# DB25-relay-HV-control.net
KiCad netlist of a schematic drawn in Altium Designer
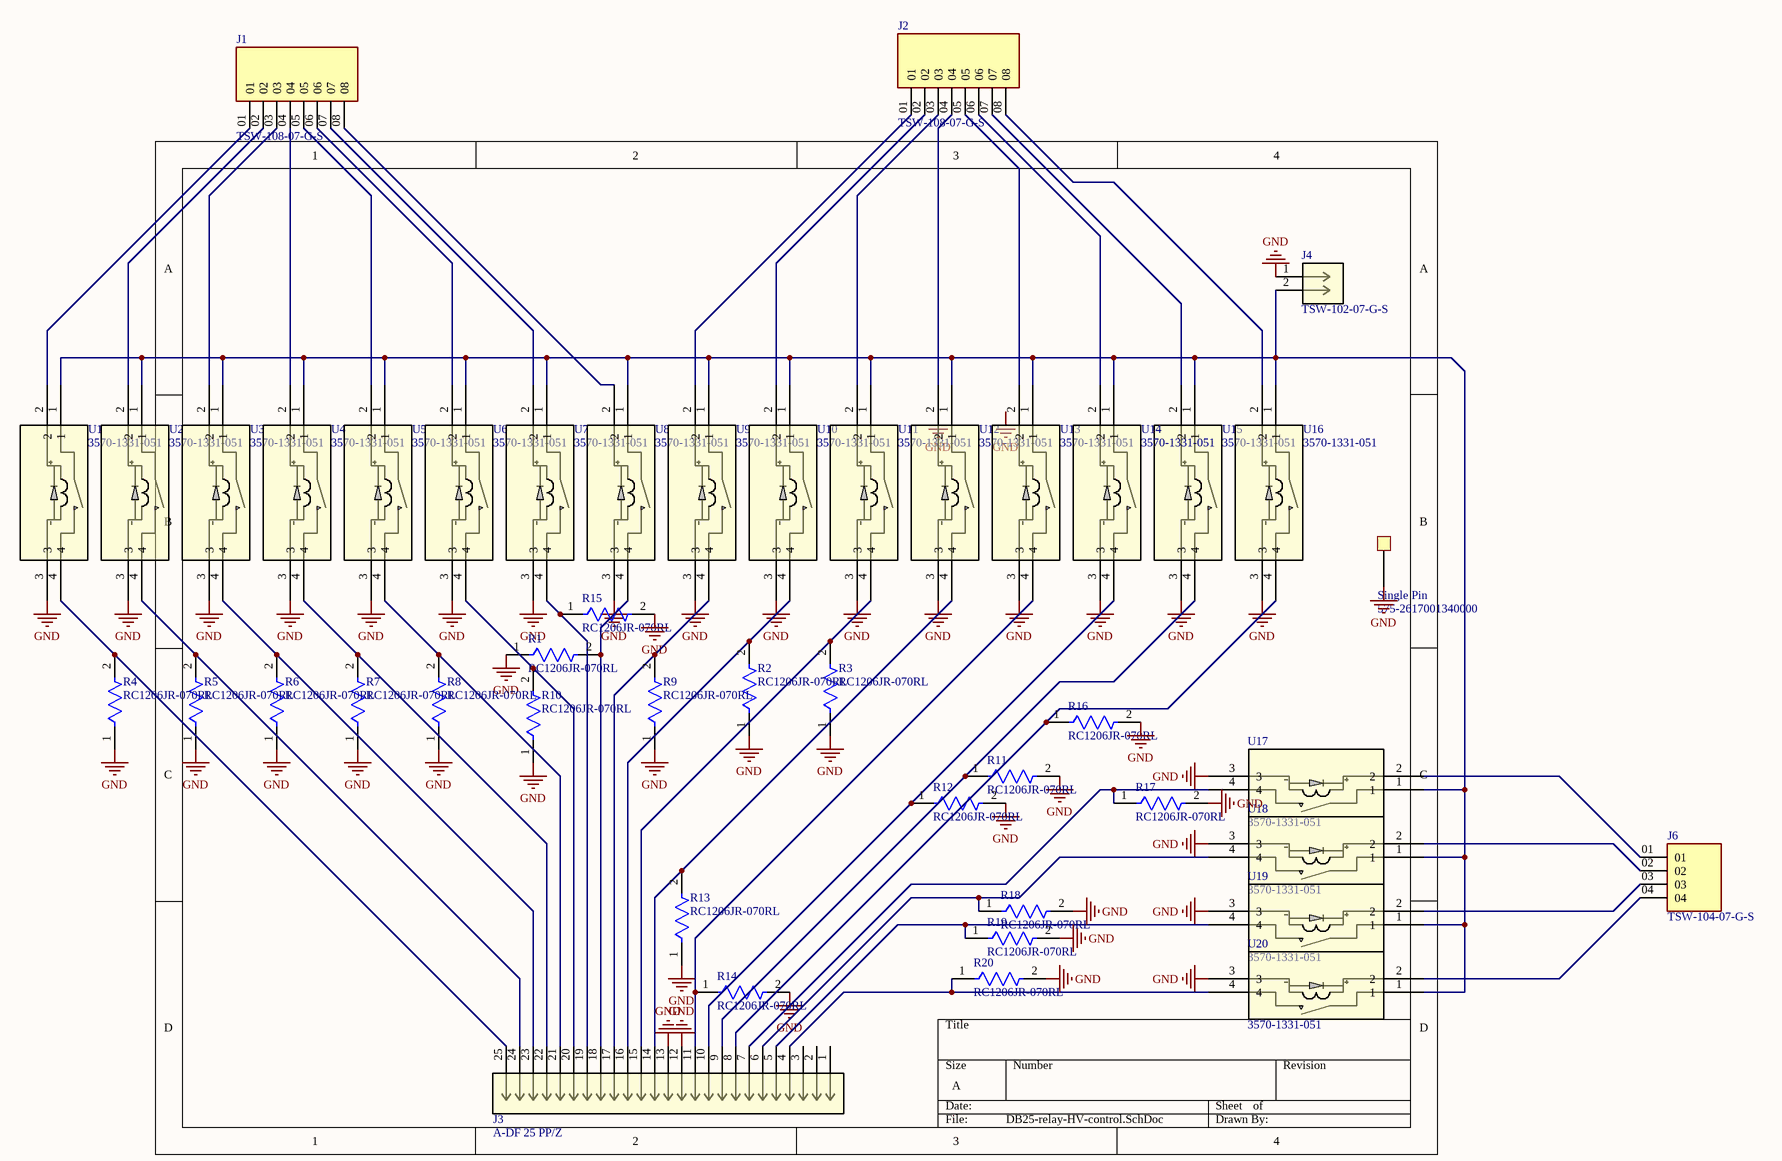
[diagram p0: DB25-relay-HV-control.SchDoc]

(export (version "E")
  (design (tool "Eeschema 10.0.6"))
  (components
    (comp (ref "J1")
      (value "TSW-108-07-G-S")
      (footprint "SAMTEC_TSW-108-07-G-S")
      (description "TSW - Samtec 2.54mm Pin Header 10.92mm Overall Pin Length (07) - Fast Stock")
      (fields (field (name "MF") "Samtec Inc."))
      (libsource (lib "SchlibLafe") (part "TSW-108-07-G-S"))
    )
    (comp (ref "J2")
      (value "TSW-108-07-G-S")
      (footprint "SAMTEC_TSW-108-07-G-S")
      (description "TSW - Samtec 2.54mm Pin Header 10.92mm Overall Pin Length (07) - Fast Stock")
      (fields (field (name "MF") "Samtec Inc."))
      (libsource (lib "SchlibLafe") (part "TSW-108-07-G-S"))
    )
    (comp (ref "J3")
      (value "A-DF 25 PP/Z")
      (footprint "CONN_A-DF 25 PPZ_ASM")
      (description "No Description Available")
      (fields (field (name "COPYRIGHT") "Copyright (C) 2024 Ultra Librarian. All rights reserved."))
      (libsource (lib "SchlibLafe") (part "A-DF 25 PPZ"))
    )
    (comp (ref "J4")
      (value "TSW-102-07-G-S")
      (footprint "CON2_1X2_TU_TSW")
      (description "No Description Available")
      (fields (field (name "COPYRIGHT") "Copyright (C) 2024 Ultra Librarian. All rights reserved."))
      (libsource (lib "SchlibLafe") (part "TSW-102-07-G-S"))
    )
    (comp (ref "J5")
      (value "Single Pin")
      (footprint "Single PC Pin")
      (fields (field (name "SUPPLIER PART NUMBER 1") "575-2617001340000"))
      (libsource (lib "SchlibLafe") (part "Single PC Pin"))
    )
    (comp (ref "J6")
      (value "TSW-104-07-G-S")
      (footprint "SAMTEC_TSW-104-07-G-S")
      (fields (field (name "MP") "altium_native_batch"))
      (libsource (lib "SchlibLafe") (part "TSW-104-07-G-S"))
    )
    (comp (ref "R1")
      (value "RC1206JR-070RL")
      (footprint "FP-RC1206-MFG")
      (description "RES SMD 0 OHM JUMPER 1/4W 1206")
      (fields
        (field (name "MANUFACTURER") "YAGEO")
        (field (name "OCTOPART") "https://octopart.com/rc1206jr-070rl-yageo-40025601")
      )
      (libsource (lib "Altium Content Vault") (part "1029c3af85768c4190bb7ad29bc67b5"))
    )
    (comp (ref "R2")
      (value "RC1206JR-070RL")
      (footprint "FP-RC1206-MFG")
      (description "RES SMD 0 OHM JUMPER 1/4W 1206")
      (fields
        (field (name "MANUFACTURER") "YAGEO")
        (field (name "OCTOPART") "https://octopart.com/rc1206jr-070rl-yageo-40025601")
      )
      (libsource (lib "Altium Content Vault") (part "1029c3af85768c4190bb7ad29bc67b5"))
    )
    (comp (ref "R3")
      (value "RC1206JR-070RL")
      (footprint "FP-RC1206-MFG")
      (description "RES SMD 0 OHM JUMPER 1/4W 1206")
      (fields
        (field (name "MANUFACTURER") "YAGEO")
        (field (name "OCTOPART") "https://octopart.com/rc1206jr-070rl-yageo-40025601")
      )
      (libsource (lib "Altium Content Vault") (part "1029c3af85768c4190bb7ad29bc67b5"))
    )
    (comp (ref "R4")
      (value "RC1206JR-070RL")
      (footprint "FP-RC1206-MFG")
      (description "RES SMD 0 OHM JUMPER 1/4W 1206")
      (fields
        (field (name "MANUFACTURER") "YAGEO")
        (field (name "OCTOPART") "https://octopart.com/rc1206jr-070rl-yageo-40025601")
      )
      (libsource (lib "Altium Content Vault") (part "1029c3af85768c4190bb7ad29bc67b5"))
    )
    (comp (ref "R5")
      (value "RC1206JR-070RL")
      (footprint "FP-RC1206-MFG")
      (description "RES SMD 0 OHM JUMPER 1/4W 1206")
      (fields
        (field (name "MANUFACTURER") "YAGEO")
        (field (name "OCTOPART") "https://octopart.com/rc1206jr-070rl-yageo-40025601")
      )
      (libsource (lib "Altium Content Vault") (part "1029c3af85768c4190bb7ad29bc67b5"))
    )
    (comp (ref "R6")
      (value "RC1206JR-070RL")
      (footprint "FP-RC1206-MFG")
      (description "RES SMD 0 OHM JUMPER 1/4W 1206")
      (fields
        (field (name "MANUFACTURER") "YAGEO")
        (field (name "OCTOPART") "https://octopart.com/rc1206jr-070rl-yageo-40025601")
      )
      (libsource (lib "Altium Content Vault") (part "1029c3af85768c4190bb7ad29bc67b5"))
    )
    (comp (ref "R7")
      (value "RC1206JR-070RL")
      (footprint "FP-RC1206-MFG")
      (description "RES SMD 0 OHM JUMPER 1/4W 1206")
      (fields
        (field (name "MANUFACTURER") "YAGEO")
        (field (name "OCTOPART") "https://octopart.com/rc1206jr-070rl-yageo-40025601")
      )
      (libsource (lib "Altium Content Vault") (part "1029c3af85768c4190bb7ad29bc67b5"))
    )
    (comp (ref "R8")
      (value "RC1206JR-070RL")
      (footprint "FP-RC1206-MFG")
      (description "RES SMD 0 OHM JUMPER 1/4W 1206")
      (fields
        (field (name "MANUFACTURER") "YAGEO")
        (field (name "OCTOPART") "https://octopart.com/rc1206jr-070rl-yageo-40025601")
      )
      (libsource (lib "Altium Content Vault") (part "1029c3af85768c4190bb7ad29bc67b5"))
    )
    (comp (ref "R9")
      (value "RC1206JR-070RL")
      (footprint "FP-RC1206-MFG")
      (description "RES SMD 0 OHM JUMPER 1/4W 1206")
      (fields
        (field (name "MANUFACTURER") "YAGEO")
        (field (name "OCTOPART") "https://octopart.com/rc1206jr-070rl-yageo-40025601")
      )
      (libsource (lib "Altium Content Vault") (part "1029c3af85768c4190bb7ad29bc67b5"))
    )
    (comp (ref "R10")
      (value "RC1206JR-070RL")
      (footprint "FP-RC1206-MFG")
      (description "RES SMD 0 OHM JUMPER 1/4W 1206")
      (fields
        (field (name "MANUFACTURER") "YAGEO")
        (field (name "OCTOPART") "https://octopart.com/rc1206jr-070rl-yageo-40025601")
      )
      (libsource (lib "Altium Content Vault") (part "1029c3af85768c4190bb7ad29bc67b5"))
    )
    (comp (ref "R11")
      (value "RC1206JR-070RL")
      (footprint "FP-RC1206-MFG")
      (description "RES SMD 0 OHM JUMPER 1/4W 1206")
      (fields
        (field (name "MANUFACTURER") "YAGEO")
        (field (name "OCTOPART") "https://octopart.com/rc1206jr-070rl-yageo-40025601")
      )
      (libsource (lib "Altium Content Vault") (part "1029c3af85768c4190bb7ad29bc67b5"))
    )
    (comp (ref "R12")
      (value "RC1206JR-070RL")
      (footprint "FP-RC1206-MFG")
      (description "RES SMD 0 OHM JUMPER 1/4W 1206")
      (fields
        (field (name "MANUFACTURER") "YAGEO")
        (field (name "OCTOPART") "https://octopart.com/rc1206jr-070rl-yageo-40025601")
      )
      (libsource (lib "Altium Content Vault") (part "1029c3af85768c4190bb7ad29bc67b5"))
    )
    (comp (ref "R13")
      (value "RC1206JR-070RL")
      (footprint "FP-RC1206-MFG")
      (description "RES SMD 0 OHM JUMPER 1/4W 1206")
      (fields
        (field (name "MANUFACTURER") "YAGEO")
        (field (name "OCTOPART") "https://octopart.com/rc1206jr-070rl-yageo-40025601")
      )
      (libsource (lib "Altium Content Vault") (part "1029c3af85768c4190bb7ad29bc67b5"))
    )
    (comp (ref "R14")
      (value "RC1206JR-070RL")
      (footprint "FP-RC1206-MFG")
      (description "RES SMD 0 OHM JUMPER 1/4W 1206")
      (fields
        (field (name "MANUFACTURER") "YAGEO")
        (field (name "OCTOPART") "https://octopart.com/rc1206jr-070rl-yageo-40025601")
      )
      (libsource (lib "Altium Content Vault") (part "1029c3af85768c4190bb7ad29bc67b5"))
    )
    (comp (ref "R15")
      (value "RC1206JR-070RL")
      (footprint "FP-RC1206-MFG")
      (description "RES SMD 0 OHM JUMPER 1/4W 1206")
      (fields
        (field (name "MANUFACTURER") "YAGEO")
        (field (name "OCTOPART") "https://octopart.com/rc1206jr-070rl-yageo-40025601")
      )
      (libsource (lib "Altium Content Vault") (part "1029c3af85768c4190bb7ad29bc67b5"))
    )
    (comp (ref "R16")
      (value "RC1206JR-070RL")
      (footprint "FP-RC1206-MFG")
      (description "RES SMD 0 OHM JUMPER 1/4W 1206")
      (fields
        (field (name "MANUFACTURER") "YAGEO")
        (field (name "OCTOPART") "https://octopart.com/rc1206jr-070rl-yageo-40025601")
      )
      (libsource (lib "Altium Content Vault") (part "1029c3af85768c4190bb7ad29bc67b5"))
    )
    (comp (ref "R17")
      (value "RC1206JR-070RL")
      (footprint "FP-RC1206-MFG")
      (description "RES SMD 0 OHM JUMPER 1/4W 1206")
      (fields
        (field (name "MANUFACTURER") "YAGEO")
        (field (name "OCTOPART") "https://octopart.com/rc1206jr-070rl-yageo-40025601")
      )
      (libsource (lib "Altium Content Vault") (part "1029c3af85768c4190bb7ad29bc67b5"))
    )
    (comp (ref "R18")
      (value "RC1206JR-070RL")
      (footprint "FP-RC1206-MFG")
      (description "RES SMD 0 OHM JUMPER 1/4W 1206")
      (fields
        (field (name "MANUFACTURER") "YAGEO")
        (field (name "OCTOPART") "https://octopart.com/rc1206jr-070rl-yageo-40025601")
      )
      (libsource (lib "Altium Content Vault") (part "1029c3af85768c4190bb7ad29bc67b5"))
    )
    (comp (ref "R19")
      (value "RC1206JR-070RL")
      (footprint "FP-RC1206-MFG")
      (description "RES SMD 0 OHM JUMPER 1/4W 1206")
      (fields
        (field (name "MANUFACTURER") "YAGEO")
        (field (name "OCTOPART") "https://octopart.com/rc1206jr-070rl-yageo-40025601")
      )
      (libsource (lib "Altium Content Vault") (part "1029c3af85768c4190bb7ad29bc67b5"))
    )
    (comp (ref "R20")
      (value "RC1206JR-070RL")
      (footprint "FP-RC1206-MFG")
      (description "RES SMD 0 OHM JUMPER 1/4W 1206")
      (fields
        (field (name "MANUFACTURER") "YAGEO")
        (field (name "OCTOPART") "https://octopart.com/rc1206jr-070rl-yageo-40025601")
      )
      (libsource (lib "Altium Content Vault") (part "1029c3af85768c4190bb7ad29bc67b5"))
    )
    (comp (ref "U1")
      (value "3570-1331-051")
      (footprint "SIP_3570-1331_COM")
      (description "No Description Available")
      (fields (field (name "COPYRIGHT") "Copyright (C) 2024 Ultra Librarian. All rights reserved."))
      (libsource (lib "") (part "3570-1331-051_2"))
    )
    (comp (ref "U2")
      (value "3570-1331-051")
      (footprint "SIP_3570-1331_COM")
      (description "No Description Available")
      (fields (field (name "COPYRIGHT") "Copyright (C) 2024 Ultra Librarian. All rights reserved."))
      (libsource (lib "") (part "3570-1331-051_3"))
    )
    (comp (ref "U3")
      (value "3570-1331-051")
      (footprint "SIP_3570-1331_COM")
      (description "No Description Available")
      (fields (field (name "COPYRIGHT") "Copyright (C) 2024 Ultra Librarian. All rights reserved."))
      (libsource (lib "") (part "3570-1331-051_1"))
    )
    (comp (ref "U4")
      (value "3570-1331-051")
      (footprint "SIP_3570-1331_COM")
      (description "No Description Available")
      (fields (field (name "COPYRIGHT") "Copyright (C) 2024 Ultra Librarian. All rights reserved."))
      (libsource (lib "") (part "3570-1331-051_1"))
    )
    (comp (ref "U5")
      (value "3570-1331-051")
      (footprint "SIP_3570-1331_COM")
      (description "No Description Available")
      (fields (field (name "COPYRIGHT") "Copyright (C) 2024 Ultra Librarian. All rights reserved."))
      (libsource (lib "") (part "3570-1331-051_1"))
    )
    (comp (ref "U6")
      (value "3570-1331-051")
      (footprint "SIP_3570-1331_COM")
      (description "No Description Available")
      (fields (field (name "COPYRIGHT") "Copyright (C) 2024 Ultra Librarian. All rights reserved."))
      (libsource (lib "") (part "3570-1331-051_1"))
    )
    (comp (ref "U7")
      (value "3570-1331-051")
      (footprint "SIP_3570-1331_COM")
      (description "No Description Available")
      (fields (field (name "COPYRIGHT") "Copyright (C) 2024 Ultra Librarian. All rights reserved."))
      (libsource (lib "") (part "3570-1331-051_1"))
    )
    (comp (ref "U8")
      (value "3570-1331-051")
      (footprint "SIP_3570-1331_COM")
      (description "No Description Available")
      (fields (field (name "COPYRIGHT") "Copyright (C) 2024 Ultra Librarian. All rights reserved."))
      (libsource (lib "") (part "3570-1331-051_1"))
    )
    (comp (ref "U9")
      (value "3570-1331-051")
      (footprint "SIP_3570-1331_COM")
      (description "No Description Available")
      (fields (field (name "COPYRIGHT") "Copyright (C) 2024 Ultra Librarian. All rights reserved."))
      (libsource (lib "") (part "3570-1331-051_1"))
    )
    (comp (ref "U10")
      (value "3570-1331-051")
      (footprint "SIP_3570-1331_COM")
      (description "No Description Available")
      (fields (field (name "COPYRIGHT") "Copyright (C) 2024 Ultra Librarian. All rights reserved."))
      (libsource (lib "") (part "3570-1331-051_1"))
    )
    (comp (ref "U11")
      (value "3570-1331-051")
      (footprint "SIP_3570-1331_COM")
      (description "No Description Available")
      (fields (field (name "COPYRIGHT") "Copyright (C) 2024 Ultra Librarian. All rights reserved."))
      (libsource (lib "") (part "3570-1331-051_1"))
    )
    (comp (ref "U12")
      (value "3570-1331-051")
      (footprint "SIP_3570-1331_COM")
      (description "No Description Available")
      (fields (field (name "COPYRIGHT") "Copyright (C) 2024 Ultra Librarian. All rights reserved."))
      (libsource (lib "") (part "3570-1331-051_1"))
    )
    (comp (ref "U13")
      (value "3570-1331-051")
      (footprint "SIP_3570-1331_COM")
      (description "No Description Available")
      (fields (field (name "COPYRIGHT") "Copyright (C) 2024 Ultra Librarian. All rights reserved."))
      (libsource (lib "") (part "3570-1331-051_1"))
    )
    (comp (ref "U14")
      (value "3570-1331-051")
      (footprint "SIP_3570-1331_COM")
      (description "No Description Available")
      (fields (field (name "COPYRIGHT") "Copyright (C) 2024 Ultra Librarian. All rights reserved."))
      (libsource (lib "") (part "3570-1331-051_1"))
    )
    (comp (ref "U15")
      (value "3570-1331-051")
      (footprint "SIP_3570-1331_COM")
      (description "No Description Available")
      (fields (field (name "COPYRIGHT") "Copyright (C) 2024 Ultra Librarian. All rights reserved."))
      (libsource (lib "") (part "3570-1331-051_1"))
    )
    (comp (ref "U16")
      (value "3570-1331-051")
      (footprint "SIP_3570-1331_COM")
      (description "No Description Available")
      (fields (field (name "COPYRIGHT") "Copyright (C) 2024 Ultra Librarian. All rights reserved."))
      (libsource (lib "") (part "3570-1331-051_1"))
    )
    (comp (ref "U17")
      (value "3570-1331-051")
      (footprint "SIP_3570-1331_COM")
      (description "No Description Available")
      (fields (field (name "COPYRIGHT") "Copyright (C) 2024 Ultra Librarian. All rights reserved."))
      (libsource (lib "SchlibAnna") (part "3570-1331-051"))
    )
    (comp (ref "U18")
      (value "3570-1331-051")
      (footprint "SIP_3570-1331_COM")
      (description "No Description Available")
      (fields (field (name "COPYRIGHT") "Copyright (C) 2024 Ultra Librarian. All rights reserved."))
      (libsource (lib "SchlibAnna") (part "3570-1331-051"))
    )
    (comp (ref "U19")
      (value "3570-1331-051")
      (footprint "SIP_3570-1331_COM")
      (description "No Description Available")
      (fields (field (name "COPYRIGHT") "Copyright (C) 2024 Ultra Librarian. All rights reserved."))
      (libsource (lib "SchlibAnna") (part "3570-1331-051"))
    )
    (comp (ref "U20")
      (value "3570-1331-051")
      (footprint "SIP_3570-1331_COM")
      (description "No Description Available")
      (fields (field (name "COPYRIGHT") "Copyright (C) 2024 Ultra Librarian. All rights reserved."))
      (libsource (lib "SchlibAnna") (part "3570-1331-051"))
    )
  )
  (nets
    (net (code "1") (name "GND") (class "Default")
      (node (ref "J3") (pin "12") (pinfunction "12_12") (pintype "passive"))
      (node (ref "J3") (pin "13") (pinfunction "13_13") (pintype "passive"))
      (node (ref "J4") (pin "1") (pinfunction "1_1") (pintype "passive"))
      (node (ref "J5") (pin "1") (pinfunction "1_1") (pintype "passive"))
      (node (ref "R1") (pin "1") (pinfunction "1_1") (pintype "passive"))
      (node (ref "R10") (pin "1") (pinfunction "1_1") (pintype "passive"))
      (node (ref "R11") (pin "2") (pinfunction "2_2") (pintype "passive"))
      (node (ref "R12") (pin "2") (pinfunction "2_2") (pintype "passive"))
      (node (ref "R13") (pin "1") (pinfunction "1_1") (pintype "passive"))
      (node (ref "R14") (pin "2") (pinfunction "2_2") (pintype "passive"))
      (node (ref "R15") (pin "2") (pinfunction "2_2") (pintype "passive"))
      (node (ref "R16") (pin "2") (pinfunction "2_2") (pintype "passive"))
      (node (ref "R17") (pin "2") (pinfunction "2_2") (pintype "passive"))
      (node (ref "R18") (pin "2") (pinfunction "2_2") (pintype "passive"))
      (node (ref "R19") (pin "2") (pinfunction "2_2") (pintype "passive"))
      (node (ref "R2") (pin "1") (pinfunction "1_1") (pintype "passive"))
      (node (ref "R20") (pin "2") (pinfunction "2_2") (pintype "passive"))
      (node (ref "R3") (pin "1") (pinfunction "1_1") (pintype "passive"))
      (node (ref "R4") (pin "1") (pinfunction "1_1") (pintype "passive"))
      (node (ref "R5") (pin "1") (pinfunction "1_1") (pintype "passive"))
      (node (ref "R6") (pin "1") (pinfunction "1_1") (pintype "passive"))
      (node (ref "R7") (pin "1") (pinfunction "1_1") (pintype "passive"))
      (node (ref "R8") (pin "1") (pinfunction "1_1") (pintype "passive"))
      (node (ref "R9") (pin "1") (pinfunction "1_1") (pintype "passive"))
      (node (ref "U1") (pin "3") (pinfunction "3_3") (pintype "passive"))
      (node (ref "U10") (pin "3") (pinfunction "3_3") (pintype "passive"))
      (node (ref "U11") (pin "3") (pinfunction "3_3") (pintype "passive"))
      (node (ref "U12") (pin "3") (pinfunction "3_3") (pintype "passive"))
      (node (ref "U13") (pin "3") (pinfunction "3_3") (pintype "passive"))
      (node (ref "U14") (pin "3") (pinfunction "3_3") (pintype "passive"))
      (node (ref "U15") (pin "3") (pinfunction "3_3") (pintype "passive"))
      (node (ref "U16") (pin "3") (pinfunction "3_3") (pintype "passive"))
      (node (ref "U17") (pin "3") (pinfunction "3_3") (pintype "passive"))
      (node (ref "U18") (pin "3") (pinfunction "3_3") (pintype "passive"))
      (node (ref "U19") (pin "3") (pinfunction "3_3") (pintype "passive"))
      (node (ref "U2") (pin "3") (pinfunction "3_3") (pintype "passive"))
      (node (ref "U20") (pin "3") (pinfunction "3_3") (pintype "passive"))
      (node (ref "U3") (pin "3") (pinfunction "3_3") (pintype "passive"))
      (node (ref "U4") (pin "3") (pinfunction "3_3") (pintype "passive"))
      (node (ref "U5") (pin "3") (pinfunction "3_3") (pintype "passive"))
      (node (ref "U6") (pin "3") (pinfunction "3_3") (pintype "passive"))
      (node (ref "U7") (pin "3") (pinfunction "3_3") (pintype "passive"))
      (node (ref "U8") (pin "3") (pinfunction "3_3") (pintype "passive"))
      (node (ref "U9") (pin "3") (pinfunction "3_3") (pintype "passive"))
    )
    (net (code "2") (name "Net-(J1-Pad01)") (class "Default")
      (node (ref "J1") (pin "01") (pinfunction "01_01") (pintype "passive"))
      (node (ref "U1") (pin "2") (pinfunction "2_2") (pintype "passive"))
    )
    (net (code "3") (name "Net-(J1-Pad02)") (class "Default")
      (node (ref "J1") (pin "02") (pinfunction "02_02") (pintype "passive"))
      (node (ref "U2") (pin "2") (pinfunction "2_2") (pintype "passive"))
    )
    (net (code "4") (name "Net-(J1-Pad03)") (class "Default")
      (node (ref "J1") (pin "03") (pinfunction "03_03") (pintype "passive"))
      (node (ref "U3") (pin "2") (pinfunction "2_2") (pintype "passive"))
    )
    (net (code "5") (name "Net-(J1-Pad04)") (class "Default")
      (node (ref "J1") (pin "04") (pinfunction "04_04") (pintype "passive"))
      (node (ref "U4") (pin "2") (pinfunction "2_2") (pintype "passive"))
    )
    (net (code "6") (name "Net-(J1-Pad05)") (class "Default")
      (node (ref "J1") (pin "05") (pinfunction "05_05") (pintype "passive"))
      (node (ref "U5") (pin "2") (pinfunction "2_2") (pintype "passive"))
    )
    (net (code "7") (name "Net-(J1-Pad06)") (class "Default")
      (node (ref "J1") (pin "06") (pinfunction "06_06") (pintype "passive"))
      (node (ref "U6") (pin "2") (pinfunction "2_2") (pintype "passive"))
    )
    (net (code "8") (name "Net-(J1-Pad07)") (class "Default")
      (node (ref "J1") (pin "07") (pinfunction "07_07") (pintype "passive"))
      (node (ref "U7") (pin "2") (pinfunction "2_2") (pintype "passive"))
    )
    (net (code "9") (name "Net-(J1-Pad08)") (class "Default")
      (node (ref "J1") (pin "08") (pinfunction "08_08") (pintype "passive"))
      (node (ref "U8") (pin "2") (pinfunction "2_2") (pintype "passive"))
    )
    (net (code "10") (name "Net-(J2-Pad01)") (class "Default")
      (node (ref "J2") (pin "01") (pinfunction "01_01") (pintype "passive"))
      (node (ref "U9") (pin "2") (pinfunction "2_2") (pintype "passive"))
    )
    (net (code "11") (name "Net-(J2-Pad02)") (class "Default")
      (node (ref "J2") (pin "02") (pinfunction "02_02") (pintype "passive"))
      (node (ref "U10") (pin "2") (pinfunction "2_2") (pintype "passive"))
    )
    (net (code "12") (name "Net-(J2-Pad03)") (class "Default")
      (node (ref "J2") (pin "03") (pinfunction "03_03") (pintype "passive"))
      (node (ref "U11") (pin "2") (pinfunction "2_2") (pintype "passive"))
    )
    (net (code "13") (name "Net-(J2-Pad04)") (class "Default")
      (node (ref "J2") (pin "04") (pinfunction "04_04") (pintype "passive"))
      (node (ref "U12") (pin "2") (pinfunction "2_2") (pintype "passive"))
    )
    (net (code "14") (name "Net-(J2-Pad05)") (class "Default")
      (node (ref "J2") (pin "05") (pinfunction "05_05") (pintype "passive"))
      (node (ref "U13") (pin "2") (pinfunction "2_2") (pintype "passive"))
    )
    (net (code "15") (name "Net-(J2-Pad06)") (class "Default")
      (node (ref "J2") (pin "06") (pinfunction "06_06") (pintype "passive"))
      (node (ref "U14") (pin "2") (pinfunction "2_2") (pintype "passive"))
    )
    (net (code "16") (name "Net-(J2-Pad07)") (class "Default")
      (node (ref "J2") (pin "07") (pinfunction "07_07") (pintype "passive"))
      (node (ref "U15") (pin "2") (pinfunction "2_2") (pintype "passive"))
    )
    (net (code "17") (name "Net-(J2-Pad08)") (class "Default")
      (node (ref "J2") (pin "08") (pinfunction "08_08") (pintype "passive"))
      (node (ref "U16") (pin "2") (pinfunction "2_2") (pintype "passive"))
    )
    (net (code "18") (name "Net-(J3-Pad4)") (class "Default")
      (node (ref "J3") (pin "4") (pinfunction "4_4") (pintype "passive"))
      (node (ref "R20") (pin "1") (pinfunction "1_1") (pintype "passive"))
      (node (ref "U20") (pin "4") (pinfunction "4_4") (pintype "passive"))
    )
    (net (code "19") (name "Net-(J3-Pad5)") (class "Default")
      (node (ref "J3") (pin "5") (pinfunction "5_5") (pintype "passive"))
      (node (ref "R19") (pin "1") (pinfunction "1_1") (pintype "passive"))
      (node (ref "U19") (pin "4") (pinfunction "4_4") (pintype "passive"))
    )
    (net (code "20") (name "Net-(J3-Pad6)") (class "Default")
      (node (ref "J3") (pin "6") (pinfunction "6_6") (pintype "passive"))
      (node (ref "R18") (pin "1") (pinfunction "1_1") (pintype "passive"))
      (node (ref "U18") (pin "4") (pinfunction "4_4") (pintype "passive"))
    )
    (net (code "21") (name "Net-(J3-Pad7)") (class "Default")
      (node (ref "J3") (pin "7") (pinfunction "7_7") (pintype "passive"))
      (node (ref "R17") (pin "1") (pinfunction "1_1") (pintype "passive"))
      (node (ref "U17") (pin "4") (pinfunction "4_4") (pintype "passive"))
    )
    (net (code "22") (name "Net-(J3-Pad8)") (class "Default")
      (node (ref "J3") (pin "8") (pinfunction "8_8") (pintype "passive"))
      (node (ref "R16") (pin "1") (pinfunction "1_1") (pintype "passive"))
      (node (ref "U16") (pin "4") (pinfunction "4_4") (pintype "passive"))
    )
    (net (code "23") (name "Net-(J3-Pad9)") (class "Default")
      (node (ref "J3") (pin "9") (pinfunction "9_9") (pintype "passive"))
      (node (ref "R11") (pin "1") (pinfunction "1_1") (pintype "passive"))
      (node (ref "U15") (pin "4") (pinfunction "4_4") (pintype "passive"))
    )
    (net (code "24") (name "Net-(J3-Pad10)") (class "Default")
      (node (ref "J3") (pin "10") (pinfunction "10_10") (pintype "passive"))
      (node (ref "R12") (pin "1") (pinfunction "1_1") (pintype "passive"))
      (node (ref "U14") (pin "4") (pinfunction "4_4") (pintype "passive"))
    )
    (net (code "25") (name "Net-(J3-Pad11)") (class "Default")
      (node (ref "J3") (pin "11") (pinfunction "11_11") (pintype "passive"))
      (node (ref "R14") (pin "1") (pinfunction "1_1") (pintype "passive"))
      (node (ref "U13") (pin "4") (pinfunction "4_4") (pintype "passive"))
    )
    (net (code "26") (name "Net-(J3-Pad14)") (class "Default")
      (node (ref "J3") (pin "14") (pinfunction "14_14") (pintype "passive"))
      (node (ref "R13") (pin "2") (pinfunction "2_2") (pintype "passive"))
      (node (ref "U12") (pin "4") (pinfunction "4_4") (pintype "passive"))
    )
    (net (code "27") (name "Net-(J3-Pad15)") (class "Default")
      (node (ref "J3") (pin "15") (pinfunction "15_15") (pintype "passive"))
      (node (ref "R3") (pin "2") (pinfunction "2_2") (pintype "passive"))
      (node (ref "U11") (pin "4") (pinfunction "4_4") (pintype "passive"))
    )
    (net (code "28") (name "Net-(J3-Pad16)") (class "Default")
      (node (ref "J3") (pin "16") (pinfunction "16_16") (pintype "passive"))
      (node (ref "R2") (pin "2") (pinfunction "2_2") (pintype "passive"))
      (node (ref "U10") (pin "4") (pinfunction "4_4") (pintype "passive"))
    )
    (net (code "29") (name "Net-(J3-Pad17)") (class "Default")
      (node (ref "J3") (pin "17") (pinfunction "17_17") (pintype "passive"))
      (node (ref "R9") (pin "2") (pinfunction "2_2") (pintype "passive"))
      (node (ref "U9") (pin "4") (pinfunction "4_4") (pintype "passive"))
    )
    (net (code "30") (name "Net-(J3-Pad18)") (class "Default")
      (node (ref "J3") (pin "18") (pinfunction "18_18") (pintype "passive"))
      (node (ref "R1") (pin "2") (pinfunction "2_2") (pintype "passive"))
      (node (ref "U8") (pin "4") (pinfunction "4_4") (pintype "passive"))
    )
    (net (code "31") (name "Net-(J3-Pad19)") (class "Default")
      (node (ref "J3") (pin "19") (pinfunction "19_19") (pintype "passive"))
      (node (ref "R15") (pin "1") (pinfunction "1_1") (pintype "passive"))
      (node (ref "U7") (pin "4") (pinfunction "4_4") (pintype "passive"))
    )
    (net (code "32") (name "Net-(J3-Pad20)") (class "Default")
      (node (ref "J3") (pin "20") (pinfunction "20_20") (pintype "passive"))
      (node (ref "R10") (pin "2") (pinfunction "2_2") (pintype "passive"))
      (node (ref "U6") (pin "4") (pinfunction "4_4") (pintype "passive"))
    )
    (net (code "33") (name "Net-(J3-Pad21)") (class "Default")
      (node (ref "J3") (pin "21") (pinfunction "21_21") (pintype "passive"))
      (node (ref "R8") (pin "2") (pinfunction "2_2") (pintype "passive"))
      (node (ref "U5") (pin "4") (pinfunction "4_4") (pintype "passive"))
    )
    (net (code "34") (name "Net-(J3-Pad22)") (class "Default")
      (node (ref "J3") (pin "22") (pinfunction "22_22") (pintype "passive"))
      (node (ref "R7") (pin "2") (pinfunction "2_2") (pintype "passive"))
      (node (ref "U4") (pin "4") (pinfunction "4_4") (pintype "passive"))
    )
    (net (code "35") (name "Net-(J3-Pad23)") (class "Default")
      (node (ref "J3") (pin "23") (pinfunction "23_23") (pintype "passive"))
      (node (ref "R6") (pin "2") (pinfunction "2_2") (pintype "passive"))
      (node (ref "U3") (pin "4") (pinfunction "4_4") (pintype "passive"))
    )
    (net (code "36") (name "Net-(J3-Pad24)") (class "Default")
      (node (ref "J3") (pin "24") (pinfunction "24_24") (pintype "passive"))
      (node (ref "R5") (pin "2") (pinfunction "2_2") (pintype "passive"))
      (node (ref "U2") (pin "4") (pinfunction "4_4") (pintype "passive"))
    )
    (net (code "37") (name "Net-(J3-Pad25)") (class "Default")
      (node (ref "J3") (pin "25") (pinfunction "25_25") (pintype "passive"))
      (node (ref "R4") (pin "2") (pinfunction "2_2") (pintype "passive"))
      (node (ref "U1") (pin "4") (pinfunction "4_4") (pintype "passive"))
    )
    (net (code "38") (name "Net-(J4-Pad2)") (class "Default")
      (node (ref "J4") (pin "2") (pinfunction "2_2") (pintype "passive"))
      (node (ref "U1") (pin "1") (pinfunction "1_1") (pintype "passive"))
      (node (ref "U10") (pin "1") (pinfunction "1_1") (pintype "passive"))
      (node (ref "U11") (pin "1") (pinfunction "1_1") (pintype "passive"))
      (node (ref "U12") (pin "1") (pinfunction "1_1") (pintype "passive"))
      (node (ref "U13") (pin "1") (pinfunction "1_1") (pintype "passive"))
      (node (ref "U14") (pin "1") (pinfunction "1_1") (pintype "passive"))
      (node (ref "U15") (pin "1") (pinfunction "1_1") (pintype "passive"))
      (node (ref "U16") (pin "1") (pinfunction "1_1") (pintype "passive"))
      (node (ref "U17") (pin "1") (pinfunction "1_1") (pintype "passive"))
      (node (ref "U18") (pin "1") (pinfunction "1_1") (pintype "passive"))
      (node (ref "U19") (pin "1") (pinfunction "1_1") (pintype "passive"))
      (node (ref "U2") (pin "1") (pinfunction "1_1") (pintype "passive"))
      (node (ref "U20") (pin "1") (pinfunction "1_1") (pintype "passive"))
      (node (ref "U3") (pin "1") (pinfunction "1_1") (pintype "passive"))
      (node (ref "U4") (pin "1") (pinfunction "1_1") (pintype "passive"))
      (node (ref "U5") (pin "1") (pinfunction "1_1") (pintype "passive"))
      (node (ref "U6") (pin "1") (pinfunction "1_1") (pintype "passive"))
      (node (ref "U7") (pin "1") (pinfunction "1_1") (pintype "passive"))
      (node (ref "U8") (pin "1") (pinfunction "1_1") (pintype "passive"))
      (node (ref "U9") (pin "1") (pinfunction "1_1") (pintype "passive"))
    )
    (net (code "39") (name "Net-(J6-Pad01)") (class "Default")
      (node (ref "J6") (pin "01") (pinfunction "01_01") (pintype "passive"))
      (node (ref "U17") (pin "2") (pinfunction "2_2") (pintype "passive"))
    )
    (net (code "40") (name "Net-(J6-Pad02)") (class "Default")
      (node (ref "J6") (pin "02") (pinfunction "02_02") (pintype "passive"))
      (node (ref "U18") (pin "2") (pinfunction "2_2") (pintype "passive"))
    )
    (net (code "41") (name "Net-(J6-Pad03)") (class "Default")
      (node (ref "J6") (pin "03") (pinfunction "03_03") (pintype "passive"))
      (node (ref "U19") (pin "2") (pinfunction "2_2") (pintype "passive"))
    )
    (net (code "42") (name "Net-(J6-Pad04)") (class "Default")
      (node (ref "J6") (pin "04") (pinfunction "04_04") (pintype "passive"))
      (node (ref "U20") (pin "2") (pinfunction "2_2") (pintype "passive"))
    )
    (net (code "43") (name "unconnected-(J3-Pad1)") (class "Default")
      (node (ref "J3") (pin "1") (pinfunction "1_1") (pintype "passive"))
    )
    (net (code "44") (name "unconnected-(J3-Pad2)") (class "Default")
      (node (ref "J3") (pin "2") (pinfunction "2_2") (pintype "passive"))
    )
    (net (code "45") (name "unconnected-(J3-Pad3)") (class "Default")
      (node (ref "J3") (pin "3") (pinfunction "3_3") (pintype "passive"))
    )
  )
)
